# main-v2.net
KiCad netlist of a schematic drawn in EAGLE
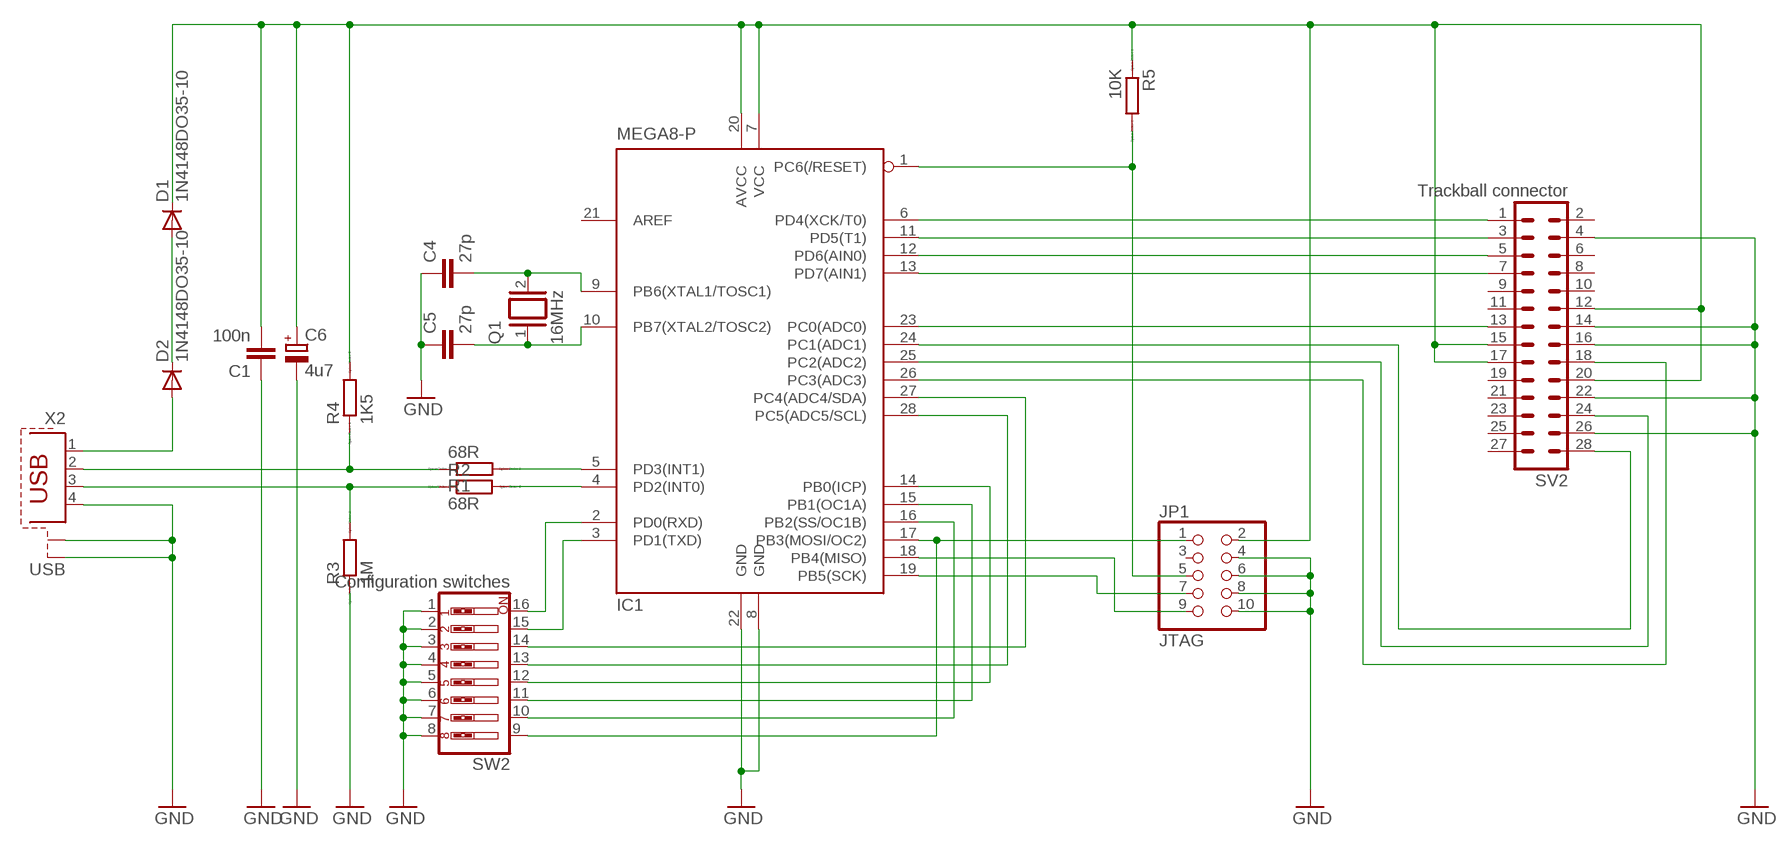
[diagram p0: schematic, sheet 1]

(export (version "E")
  (design (tool "Eeschema 10.0.6"))
  (components
    (comp (ref "C1")
      (value "100n")
      (footprint "eagle-import:C025-025X050")
      (libsource (lib "eagle-import") (part "C-EU025-025X050"))
    )
    (comp (ref "C4")
      (value "27p")
      (footprint "eagle-import:C025-025X050")
      (libsource (lib "eagle-import") (part "C-EU025-025X050"))
    )
    (comp (ref "C5")
      (value "27p")
      (footprint "eagle-import:C025-025X050")
      (libsource (lib "eagle-import") (part "C-EU025-025X050"))
    )
    (comp (ref "C6")
      (value "4u7")
      (footprint "eagle-import:E2,5-5")
      (libsource (lib "eagle-import") (part "CPOL-EUE2.5-5"))
    )
    (comp (ref "D1")
      (value "1N4148DO35-10")
      (footprint "eagle-import:DO35-10")
      (libsource (lib "eagle-import") (part "1N4148DO35-10"))
    )
    (comp (ref "D2")
      (value "1N4148DO35-10")
      (footprint "eagle-import:DO35-10")
      (libsource (lib "eagle-import") (part "1N4148DO35-10"))
    )
    (comp (ref "IC1")
      (value "MEGA8-P")
      (footprint "eagle-import:DIL28-3")
      (libsource (lib "eagle-import") (part "MEGA8-P"))
    )
    (comp (ref "JP1")
      (value "JTAG")
      (footprint "eagle-import:2X05")
      (libsource (lib "eagle-import") (part "PINHD-2X5"))
    )
    (comp (ref "Q1")
      (value "16MHz")
      (footprint "eagle-import:QS")
      (libsource (lib "eagle-import") (part "XTAL/S"))
    )
    (comp (ref "R1")
      (value "68R")
      (footprint "eagle-import:0207_10")
      (libsource (lib "eagle-import") (part "R0207/10"))
    )
    (comp (ref "R2")
      (value "68R")
      (footprint "eagle-import:0207_10")
      (libsource (lib "eagle-import") (part "R0207/10"))
    )
    (comp (ref "R3")
      (value "1M")
      (footprint "eagle-import:0207_10")
      (libsource (lib "eagle-import") (part "R0207/10"))
    )
    (comp (ref "R4")
      (value "1K5")
      (footprint "eagle-import:0207_10")
      (libsource (lib "eagle-import") (part "R0207/10"))
    )
    (comp (ref "R5")
      (value "10K")
      (footprint "eagle-import:0207_10")
      (libsource (lib "eagle-import") (part "R0207/10"))
    )
    (comp (ref "SV2")
      (value "Trackball connector")
      (footprint "eagle-import:MA14-2")
      (libsource (lib "eagle-import") (part "MA14-214"))
    )
    (comp (ref "SW2")
      (value "Configuration switches")
      (footprint "eagle-import:EDG-08")
      (libsource (lib "eagle-import") (part "SW_DIP-8"))
    )
    (comp (ref "X2")
      (value "USB")
      (footprint "eagle-import:PN61729-S")
      (libsource (lib "eagle-import") (part "PN61729-S"))
    )
  )
  (nets
    (net (code "1") (name "GND") (class "Default")
      (node (ref "C1") (pin "1") (pinfunction "1_1") (pintype "passive"))
      (node (ref "C4") (pin "1") (pinfunction "1_1") (pintype "passive"))
      (node (ref "C5") (pin "1") (pinfunction "1_1") (pintype "passive"))
      (node (ref "C6") (pin "-") (pinfunction "-_-") (pintype "passive"))
      (node (ref "IC1") (pin "22") (pinfunction "GND_22") (pintype "power_in"))
      (node (ref "IC1") (pin "8") (pinfunction "GND_8") (pintype "power_in"))
      (node (ref "JP1") (pin "10") (pinfunction "10_10") (pintype "passive"))
      (node (ref "JP1") (pin "4") (pinfunction "4_4") (pintype "passive"))
      (node (ref "JP1") (pin "6") (pinfunction "6_6") (pintype "passive"))
      (node (ref "JP1") (pin "8") (pinfunction "8_8") (pintype "passive"))
      (node (ref "R3") (pin "1") (pinfunction "1_1") (pintype "passive"))
      (node (ref "SV2") (pin "14") (pinfunction "14_14") (pintype "passive"))
      (node (ref "SV2") (pin "16") (pinfunction "16_16") (pintype "passive"))
      (node (ref "SV2") (pin "22") (pinfunction "22_22") (pintype "passive"))
      (node (ref "SV2") (pin "26") (pinfunction "26_26") (pintype "passive"))
      (node (ref "SV2") (pin "4") (pinfunction "4_4") (pintype "passive"))
      (node (ref "SW2") (pin "1") (pinfunction "1_1") (pintype "passive"))
      (node (ref "SW2") (pin "2") (pinfunction "2_2") (pintype "passive"))
      (node (ref "SW2") (pin "3") (pinfunction "3_3") (pintype "passive"))
      (node (ref "SW2") (pin "4") (pinfunction "4_4") (pintype "passive"))
      (node (ref "SW2") (pin "5") (pinfunction "5_5") (pintype "passive"))
      (node (ref "SW2") (pin "6") (pinfunction "6_6") (pintype "passive"))
      (node (ref "SW2") (pin "7") (pinfunction "7_7") (pintype "passive"))
      (node (ref "SW2") (pin "8") (pinfunction "8_8") (pintype "passive"))
      (node (ref "X2") (pin "4") (pinfunction "4_4") (pintype "passive"))
      (node (ref "X2") (pin "S1") (pinfunction "S1_S1") (pintype "passive"))
      (node (ref "X2") (pin "S2") (pinfunction "S2_S2") (pintype "passive"))
    )
    (net (code "2") (name "Net-(D1-PadA)") (class "Default")
      (node (ref "D1") (pin "A") (pinfunction "A_A") (pintype "passive"))
      (node (ref "D2") (pin "C") (pinfunction "C_C") (pintype "passive"))
    )
    (net (code "3") (name "Net-(D2-PadA)") (class "Default")
      (node (ref "D2") (pin "A") (pinfunction "A_A") (pintype "passive"))
      (node (ref "X2") (pin "1") (pinfunction "1_1") (pintype "passive"))
    )
    (net (code "4") (name "Net-(IC1-AVCC)") (class "Default")
      (node (ref "C1") (pin "2") (pinfunction "2_2") (pintype "passive"))
      (node (ref "C6") (pin "+") (pinfunction "+_+") (pintype "passive"))
      (node (ref "D1") (pin "C") (pinfunction "C_C") (pintype "passive"))
      (node (ref "IC1") (pin "20") (pinfunction "AVCC_20") (pintype "power_in"))
      (node (ref "IC1") (pin "7") (pinfunction "VCC_7") (pintype "power_in"))
      (node (ref "JP1") (pin "2") (pinfunction "2_2") (pintype "passive"))
      (node (ref "R4") (pin "2") (pinfunction "2_2") (pintype "passive"))
      (node (ref "R5") (pin "1") (pinfunction "1_1") (pintype "passive"))
      (node (ref "SV2") (pin "12") (pinfunction "12_12") (pintype "passive"))
      (node (ref "SV2") (pin "15") (pinfunction "15_15") (pintype "passive"))
      (node (ref "SV2") (pin "17") (pinfunction "17_17") (pintype "passive"))
      (node (ref "SV2") (pin "20") (pinfunction "20_20") (pintype "passive"))
    )
    (net (code "5") (name "Net-(IC1-PB0(ICP))") (class "Default")
      (node (ref "IC1") (pin "14") (pinfunction "PB0(ICP)_14") (pintype "bidirectional"))
      (node (ref "SW2") (pin "12") (pinfunction "12_12") (pintype "passive"))
    )
    (net (code "6") (name "Net-(IC1-PB1(OC1A))") (class "Default")
      (node (ref "IC1") (pin "15") (pinfunction "PB1(OC1A)_15") (pintype "bidirectional"))
      (node (ref "SW2") (pin "11") (pinfunction "11_11") (pintype "passive"))
    )
    (net (code "7") (name "Net-(IC1-PB2(SS{slash}OC1B))") (class "Default")
      (node (ref "IC1") (pin "16") (pinfunction "PB2(SS/OC1B)_16") (pintype "bidirectional"))
      (node (ref "SW2") (pin "10") (pinfunction "10_10") (pintype "passive"))
    )
    (net (code "8") (name "Net-(IC1-PB3(MOSI{slash}OC2))") (class "Default")
      (node (ref "IC1") (pin "17") (pinfunction "PB3(MOSI/OC2)_17") (pintype "bidirectional"))
      (node (ref "JP1") (pin "1") (pinfunction "1_1") (pintype "passive"))
      (node (ref "SW2") (pin "9") (pinfunction "9_9") (pintype "passive"))
    )
    (net (code "9") (name "Net-(IC1-PB4(MISO))") (class "Default")
      (node (ref "IC1") (pin "18") (pinfunction "PB4(MISO)_18") (pintype "bidirectional"))
      (node (ref "JP1") (pin "9") (pinfunction "9_9") (pintype "passive"))
    )
    (net (code "10") (name "Net-(IC1-PB5(SCK))") (class "Default")
      (node (ref "IC1") (pin "19") (pinfunction "PB5(SCK)_19") (pintype "bidirectional"))
      (node (ref "JP1") (pin "7") (pinfunction "7_7") (pintype "passive"))
    )
    (net (code "11") (name "Net-(IC1-PB6(XTAL1{slash}TOSC1))") (class "Default")
      (node (ref "C4") (pin "2") (pinfunction "2_2") (pintype "passive"))
      (node (ref "IC1") (pin "9") (pinfunction "PB6(XTAL1/TOSC1)_9") (pintype "bidirectional"))
      (node (ref "Q1") (pin "2") (pinfunction "2_2") (pintype "passive"))
    )
    (net (code "12") (name "Net-(IC1-PB7(XTAL2{slash}TOSC2))") (class "Default")
      (node (ref "C5") (pin "2") (pinfunction "2_2") (pintype "passive"))
      (node (ref "IC1") (pin "10") (pinfunction "PB7(XTAL2/TOSC2)_10") (pintype "bidirectional"))
      (node (ref "Q1") (pin "1") (pinfunction "1_1") (pintype "passive"))
    )
    (net (code "13") (name "Net-(IC1-PC0(ADC0))") (class "Default")
      (node (ref "IC1") (pin "23") (pinfunction "PC0(ADC0)_23") (pintype "bidirectional"))
      (node (ref "SV2") (pin "13") (pinfunction "13_13") (pintype "passive"))
    )
    (net (code "14") (name "Net-(IC1-PC1(ADC1))") (class "Default")
      (node (ref "IC1") (pin "24") (pinfunction "PC1(ADC1)_24") (pintype "bidirectional"))
      (node (ref "SV2") (pin "28") (pinfunction "28_28") (pintype "passive"))
    )
    (net (code "15") (name "Net-(IC1-PC2(ADC2))") (class "Default")
      (node (ref "IC1") (pin "25") (pinfunction "PC2(ADC2)_25") (pintype "bidirectional"))
      (node (ref "SV2") (pin "24") (pinfunction "24_24") (pintype "passive"))
    )
    (net (code "16") (name "Net-(IC1-PC3(ADC3))") (class "Default")
      (node (ref "IC1") (pin "26") (pinfunction "PC3(ADC3)_26") (pintype "bidirectional"))
      (node (ref "SV2") (pin "18") (pinfunction "18_18") (pintype "passive"))
    )
    (net (code "17") (name "Net-(IC1-PC4(ADC4{slash}SDA))") (class "Default")
      (node (ref "IC1") (pin "27") (pinfunction "PC4(ADC4/SDA)_27") (pintype "bidirectional"))
      (node (ref "SW2") (pin "14") (pinfunction "14_14") (pintype "passive"))
    )
    (net (code "18") (name "Net-(IC1-PC5(ADC5{slash}SCL))") (class "Default")
      (node (ref "IC1") (pin "28") (pinfunction "PC5(ADC5/SCL)_28") (pintype "bidirectional"))
      (node (ref "SW2") (pin "13") (pinfunction "13_13") (pintype "passive"))
    )
    (net (code "19") (name "Net-(IC1-PC6({slash}RESET))") (class "Default")
      (node (ref "IC1") (pin "1") (pinfunction "PC6(/RESET)_1") (pintype "bidirectional"))
      (node (ref "JP1") (pin "5") (pinfunction "5_5") (pintype "passive"))
      (node (ref "R5") (pin "2") (pinfunction "2_2") (pintype "passive"))
    )
    (net (code "20") (name "Net-(IC1-PD0(RXD))") (class "Default")
      (node (ref "IC1") (pin "2") (pinfunction "PD0(RXD)_2") (pintype "bidirectional"))
      (node (ref "SW2") (pin "16") (pinfunction "16_16") (pintype "passive"))
    )
    (net (code "21") (name "Net-(IC1-PD1(TXD))") (class "Default")
      (node (ref "IC1") (pin "3") (pinfunction "PD1(TXD)_3") (pintype "bidirectional"))
      (node (ref "SW2") (pin "15") (pinfunction "15_15") (pintype "passive"))
    )
    (net (code "22") (name "Net-(IC1-PD2(INT0))") (class "Default")
      (node (ref "IC1") (pin "4") (pinfunction "PD2(INT0)_4") (pintype "bidirectional"))
      (node (ref "R2") (pin "2") (pinfunction "2_2") (pintype "passive"))
    )
    (net (code "23") (name "Net-(IC1-PD3(INT1))") (class "Default")
      (node (ref "IC1") (pin "5") (pinfunction "PD3(INT1)_5") (pintype "bidirectional"))
      (node (ref "R1") (pin "2") (pinfunction "2_2") (pintype "passive"))
    )
    (net (code "24") (name "Net-(IC1-PD4(XCK{slash}T0))") (class "Default")
      (node (ref "IC1") (pin "6") (pinfunction "PD4(XCK/T0)_6") (pintype "bidirectional"))
      (node (ref "SV2") (pin "1") (pinfunction "1_1") (pintype "passive"))
    )
    (net (code "25") (name "Net-(IC1-PD5(T1))") (class "Default")
      (node (ref "IC1") (pin "11") (pinfunction "PD5(T1)_11") (pintype "bidirectional"))
      (node (ref "SV2") (pin "3") (pinfunction "3_3") (pintype "passive"))
    )
    (net (code "26") (name "Net-(IC1-PD6(AIN0))") (class "Default")
      (node (ref "IC1") (pin "12") (pinfunction "PD6(AIN0)_12") (pintype "bidirectional"))
      (node (ref "SV2") (pin "5") (pinfunction "5_5") (pintype "passive"))
    )
    (net (code "27") (name "Net-(IC1-PD7(AIN1))") (class "Default")
      (node (ref "IC1") (pin "13") (pinfunction "PD7(AIN1)_13") (pintype "bidirectional"))
      (node (ref "SV2") (pin "7") (pinfunction "7_7") (pintype "passive"))
    )
    (net (code "28") (name "Net-(R1-Pad1)") (class "Default")
      (node (ref "R1") (pin "1") (pinfunction "1_1") (pintype "passive"))
      (node (ref "R4") (pin "1") (pinfunction "1_1") (pintype "passive"))
      (node (ref "X2") (pin "2") (pinfunction "2_2") (pintype "passive"))
    )
    (net (code "29") (name "Net-(R2-Pad1)") (class "Default")
      (node (ref "R2") (pin "1") (pinfunction "1_1") (pintype "passive"))
      (node (ref "R3") (pin "2") (pinfunction "2_2") (pintype "passive"))
      (node (ref "X2") (pin "3") (pinfunction "3_3") (pintype "passive"))
    )
    (net (code "30") (name "unconnected-(IC1-AREF-Pad21)") (class "Default")
      (node (ref "IC1") (pin "21") (pinfunction "AREF_21") (pintype "passive"))
    )
    (net (code "31") (name "unconnected-(JP1-Pad3)") (class "Default")
      (node (ref "JP1") (pin "3") (pinfunction "3_3") (pintype "passive"))
    )
    (net (code "32") (name "unconnected-(SV2-Pad2)") (class "Default")
      (node (ref "SV2") (pin "2") (pinfunction "2_2") (pintype "passive"))
    )
    (net (code "33") (name "unconnected-(SV2-Pad6)") (class "Default")
      (node (ref "SV2") (pin "6") (pinfunction "6_6") (pintype "passive"))
    )
    (net (code "34") (name "unconnected-(SV2-Pad8)") (class "Default")
      (node (ref "SV2") (pin "8") (pinfunction "8_8") (pintype "passive"))
    )
    (net (code "35") (name "unconnected-(SV2-Pad9)") (class "Default")
      (node (ref "SV2") (pin "9") (pinfunction "9_9") (pintype "passive"))
    )
    (net (code "36") (name "unconnected-(SV2-Pad10)") (class "Default")
      (node (ref "SV2") (pin "10") (pinfunction "10_10") (pintype "passive"))
    )
    (net (code "37") (name "unconnected-(SV2-Pad11)") (class "Default")
      (node (ref "SV2") (pin "11") (pinfunction "11_11") (pintype "passive"))
    )
    (net (code "38") (name "unconnected-(SV2-Pad19)") (class "Default")
      (node (ref "SV2") (pin "19") (pinfunction "19_19") (pintype "passive"))
    )
    (net (code "39") (name "unconnected-(SV2-Pad21)") (class "Default")
      (node (ref "SV2") (pin "21") (pinfunction "21_21") (pintype "passive"))
    )
    (net (code "40") (name "unconnected-(SV2-Pad23)") (class "Default")
      (node (ref "SV2") (pin "23") (pinfunction "23_23") (pintype "passive"))
    )
    (net (code "41") (name "unconnected-(SV2-Pad25)") (class "Default")
      (node (ref "SV2") (pin "25") (pinfunction "25_25") (pintype "passive"))
    )
    (net (code "42") (name "unconnected-(SV2-Pad27)") (class "Default")
      (node (ref "SV2") (pin "27") (pinfunction "27_27") (pintype "passive"))
    )
  )
)
